# 30x70-motor-controller.net
KiCad netlist of a schematic drawn in EAGLE
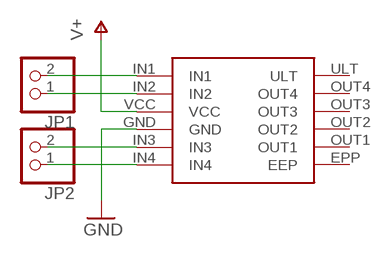
[diagram p0: schematic, sheet 1]
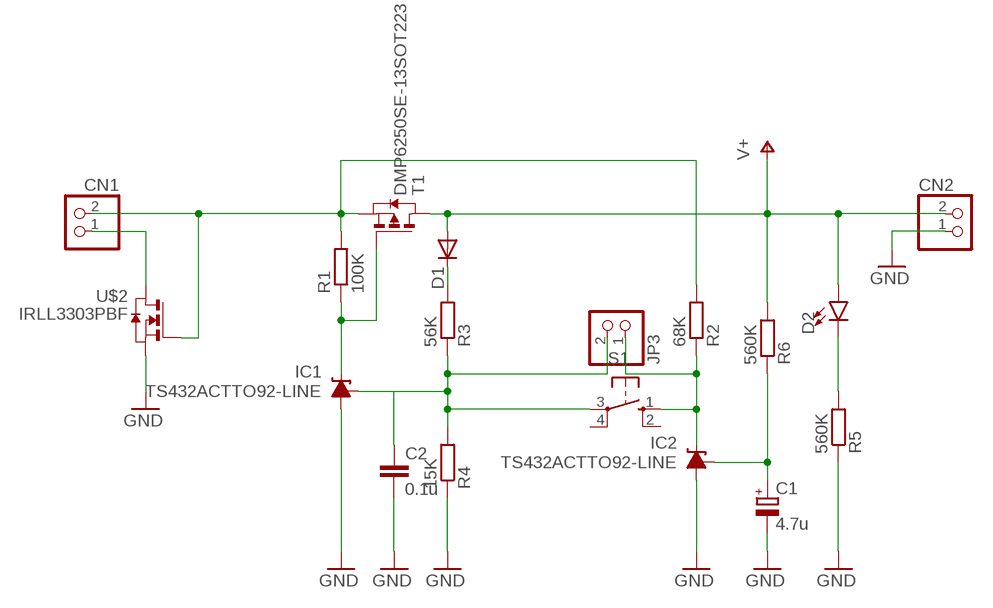
[diagram p1: schematic, sheet 2]

(export (version "E")
  (design (tool "Eeschema 10.0.6"))
  (components
    (comp (ref "JP1")
      (value "PINHD-1X2/90")
      (footprint "eagle-import:1X02_90")
      (libsource (lib "eagle-import") (part "PINHD-1X2/90"))
    )
    (comp (ref "JP2")
      (value "PINHD-1X2/90")
      (footprint "eagle-import:1X02_90")
      (libsource (lib "eagle-import") (part "PINHD-1X2/90"))
    )
    (comp (ref "U$1")
      (value "DRV8833-MODULE")
      (footprint "eagle-import:DRV8833-BRKOUT")
      (libsource (lib "eagle-import") (part "DRV8833-MODULE"))
    )
    (comp (ref "C1")
      (value "4.7u")
      (footprint "eagle-import:E2,5-5")
      (libsource (lib "eagle-import") (part "CPOL-EUE2.5-5"))
    )
    (comp (ref "C2")
      (value "0.1u")
      (footprint "eagle-import:C025-024X044")
      (libsource (lib "eagle-import") (part "C-EU025-024X044"))
    )
    (comp (ref "CN1")
      (value "JST_2PIN-THM-RA")
      (footprint "eagle-import:JST-PH-2-THM-RA")
      (libsource (lib "eagle-import") (part "JST_2PIN-THM-RA"))
    )
    (comp (ref "CN2")
      (value "JST_2PIN-THM-RA")
      (footprint "eagle-import:JST-PH-2-THM-RA")
      (libsource (lib "eagle-import") (part "JST_2PIN-THM-RA"))
    )
    (comp (ref "D1")
      (value "DIODE-D-2.5")
      (footprint "eagle-import:D-2.5")
      (libsource (lib "eagle-import") (part "DIODE-D-2.5"))
    )
    (comp (ref "D2")
      (value "LED-3MM-NO_SILK")
      (footprint "eagle-import:LED_3MM-NS")
      (libsource (lib "eagle-import") (part "LED-3MM-NO_SILK"))
    )
    (comp (ref "IC1")
      (value "TS432ACTTO92-LINE")
      (footprint "eagle-import:TO92-LINE")
      (libsource (lib "eagle-import") (part "TS432ACTTO92-LINE"))
    )
    (comp (ref "IC2")
      (value "TS432ACTTO92-LINE")
      (footprint "eagle-import:TO92-LINE")
      (libsource (lib "eagle-import") (part "TS432ACTTO92-LINE"))
    )
    (comp (ref "JP3")
      (value "PINHD-1X2/90")
      (footprint "eagle-import:1X02_90")
      (libsource (lib "eagle-import") (part "PINHD-1X2/90"))
    )
    (comp (ref "R1")
      (value "100K")
      (footprint "eagle-import:0204_5")
      (libsource (lib "eagle-import") (part "R-EU_0204/5"))
    )
    (comp (ref "R2")
      (value "68K")
      (footprint "eagle-import:0204_5")
      (libsource (lib "eagle-import") (part "R-EU_0204/5"))
    )
    (comp (ref "R3")
      (value "56K")
      (footprint "eagle-import:0204_5")
      (libsource (lib "eagle-import") (part "R-EU_0204/5"))
    )
    (comp (ref "R4")
      (value "15K")
      (footprint "eagle-import:0204V")
      (libsource (lib "eagle-import") (part "R-EU_0204/2V"))
    )
    (comp (ref "R5")
      (value "560K")
      (footprint "eagle-import:0204_5")
      (libsource (lib "eagle-import") (part "R-EU_0204/5"))
    )
    (comp (ref "R6")
      (value "560K")
      (footprint "eagle-import:0204_5")
      (libsource (lib "eagle-import") (part "R-EU_0204/5"))
    )
    (comp (ref "S1")
      (value "10-XX")
      (footprint "eagle-import:B3F-10XX")
      (fields (field (name "MPN") "B3F-1000"))
      (libsource (lib "eagle-import") (part "10-XX"))
    )
    (comp (ref "T1")
      (value "DMP6250SE-13SOT223")
      (footprint "eagle-import:SOT223")
      (libsource (lib "eagle-import") (part "DMP6250SE-13SOT223"))
    )
    (comp (ref "U$2")
      (value "IRLL3303PBF")
      (footprint "eagle-import:SOT223")
      (libsource (lib "eagle-import") (part "IRLL3303PBF"))
    )
  )
  (nets
    (net (code "1") (name "GND") (class "Default")
      (node (ref "C1") (pin "-") (pinfunction "-_-") (pintype "passive"))
      (node (ref "C2") (pin "2") (pinfunction "2_2") (pintype "passive"))
      (node (ref "CN2") (pin "1") (pinfunction "2_1") (pintype "passive"))
      (node (ref "IC1") (pin "2") (pinfunction "A_2") (pintype "passive"))
      (node (ref "IC2") (pin "2") (pinfunction "A_2") (pintype "passive"))
      (node (ref "R4") (pin "1") (pinfunction "1_1") (pintype "passive"))
      (node (ref "R5") (pin "1") (pinfunction "1_1") (pintype "passive"))
      (node (ref "U$1") (pin "GND") (pinfunction "GND_GND") (pintype "bidirectional"))
      (node (ref "U$2") (pin "3") (pinfunction "S_3") (pintype "passive"))
    )
    (net (code "2") (name "Net-(CN1-1)") (class "Default")
      (node (ref "CN1") (pin "2") (pinfunction "1_2") (pintype "passive"))
      (node (ref "R1") (pin "2") (pinfunction "2_2") (pintype "passive"))
      (node (ref "R2") (pin "2") (pinfunction "2_2") (pintype "passive"))
      (node (ref "T1") (pin "3") (pinfunction "S_3") (pintype "passive"))
      (node (ref "U$2") (pin "1") (pinfunction "G_1") (pintype "passive"))
    )
    (net (code "3") (name "Net-(CN1-2)") (class "Default")
      (node (ref "CN1") (pin "1") (pinfunction "2_1") (pintype "passive"))
      (node (ref "U$2") (pin "2") (pinfunction "D_2") (pintype "passive"))
      (node (ref "U$2") (pin "4") (pinfunction "D_4") (pintype "passive"))
    )
    (net (code "4") (name "Net-(D1-PadC)") (class "Default")
      (node (ref "D1") (pin "C") (pinfunction "C_C") (pintype "passive"))
      (node (ref "R3") (pin "2") (pinfunction "2_2") (pintype "passive"))
    )
    (net (code "5") (name "Net-(D2-C)") (class "Default")
      (node (ref "D2") (pin "K") (pinfunction "C_K") (pintype "passive"))
      (node (ref "R5") (pin "2") (pinfunction "2_2") (pintype "passive"))
    )
    (net (code "6") (name "Net-(IC1-C)") (class "Default")
      (node (ref "IC1") (pin "1") (pinfunction "C_1") (pintype "passive"))
      (node (ref "R1") (pin "1") (pinfunction "1_1") (pintype "passive"))
      (node (ref "T1") (pin "1") (pinfunction "G_1") (pintype "passive"))
    )
    (net (code "7") (name "Net-(IC1-FB)") (class "Default")
      (node (ref "C2") (pin "1") (pinfunction "1_1") (pintype "passive"))
      (node (ref "IC1") (pin "3") (pinfunction "FB_3") (pintype "passive"))
      (node (ref "JP3") (pin "2") (pinfunction "2_2") (pintype "passive"))
      (node (ref "R3") (pin "1") (pinfunction "1_1") (pintype "passive"))
      (node (ref "R4") (pin "2") (pinfunction "2_2") (pintype "passive"))
      (node (ref "S1") (pin "3") (pinfunction "P_3") (pintype "passive"))
    )
    (net (code "8") (name "Net-(IC2-C)") (class "Default")
      (node (ref "IC2") (pin "1") (pinfunction "C_1") (pintype "passive"))
      (node (ref "JP3") (pin "1") (pinfunction "1_1") (pintype "passive"))
      (node (ref "R2") (pin "1") (pinfunction "1_1") (pintype "passive"))
      (node (ref "S1") (pin "1") (pinfunction "S_1") (pintype "passive"))
    )
    (net (code "9") (name "Net-(IC2-FB)") (class "Default")
      (node (ref "C1") (pin "+") (pinfunction "+_+") (pintype "passive"))
      (node (ref "IC2") (pin "3") (pinfunction "FB_3") (pintype "passive"))
      (node (ref "R6") (pin "1") (pinfunction "1_1") (pintype "passive"))
    )
    (net (code "10") (name "Net-(JP1-Pad1)") (class "Default")
      (node (ref "JP1") (pin "1") (pinfunction "1_1") (pintype "passive"))
      (node (ref "U$1") (pin "IN2") (pinfunction "IN2_IN2") (pintype "bidirectional"))
    )
    (net (code "11") (name "Net-(JP1-Pad2)") (class "Default")
      (node (ref "JP1") (pin "2") (pinfunction "2_2") (pintype "passive"))
      (node (ref "U$1") (pin "IN1") (pinfunction "IN1_IN1") (pintype "bidirectional"))
    )
    (net (code "12") (name "Net-(JP2-Pad1)") (class "Default")
      (node (ref "JP2") (pin "1") (pinfunction "1_1") (pintype "passive"))
      (node (ref "U$1") (pin "IN4") (pinfunction "IN4_IN4") (pintype "bidirectional"))
    )
    (net (code "13") (name "Net-(JP2-Pad2)") (class "Default")
      (node (ref "JP2") (pin "2") (pinfunction "2_2") (pintype "passive"))
      (node (ref "U$1") (pin "IN3") (pinfunction "IN3_IN3") (pintype "bidirectional"))
    )
    (net (code "14") (name "V+") (class "Default")
      (node (ref "CN2") (pin "2") (pinfunction "1_2") (pintype "passive"))
      (node (ref "D1") (pin "A") (pinfunction "A_A") (pintype "passive"))
      (node (ref "D2") (pin "A") (pinfunction "A_A") (pintype "passive"))
      (node (ref "R6") (pin "2") (pinfunction "2_2") (pintype "passive"))
      (node (ref "T1") (pin "2") (pinfunction "D_2") (pintype "passive"))
      (node (ref "T1") (pin "4") (pinfunction "D_4") (pintype "passive"))
      (node (ref "U$1") (pin "VCC") (pinfunction "VCC_VCC") (pintype "bidirectional"))
    )
    (net (code "15") (name "unconnected-(S1-P1-Pad4)") (class "Default")
      (node (ref "S1") (pin "4") (pinfunction "P1_4") (pintype "passive"))
    )
    (net (code "16") (name "unconnected-(S1-S1-Pad2)") (class "Default")
      (node (ref "S1") (pin "2") (pinfunction "S1_2") (pintype "passive"))
    )
    (net (code "17") (name "unconnected-(U$1-EEP-PadEPP)") (class "Default")
      (node (ref "U$1") (pin "EPP") (pinfunction "EEP_EPP") (pintype "bidirectional"))
    )
    (net (code "18") (name "unconnected-(U$1-PadOUT1)") (class "Default")
      (node (ref "U$1") (pin "OUT1") (pinfunction "OUT1_OUT1") (pintype "bidirectional"))
    )
    (net (code "19") (name "unconnected-(U$1-PadOUT2)") (class "Default")
      (node (ref "U$1") (pin "OUT2") (pinfunction "OUT2_OUT2") (pintype "bidirectional"))
    )
    (net (code "20") (name "unconnected-(U$1-PadOUT3)") (class "Default")
      (node (ref "U$1") (pin "OUT3") (pinfunction "OUT3_OUT3") (pintype "bidirectional"))
    )
    (net (code "21") (name "unconnected-(U$1-PadOUT4)") (class "Default")
      (node (ref "U$1") (pin "OUT4") (pinfunction "OUT4_OUT4") (pintype "bidirectional"))
    )
    (net (code "22") (name "unconnected-(U$1-PadULT)") (class "Default")
      (node (ref "U$1") (pin "ULT") (pinfunction "ULT_ULT") (pintype "bidirectional"))
    )
  )
)
